# InPortIndication.net
KiCad netlist of a schematic drawn in Altium Designer
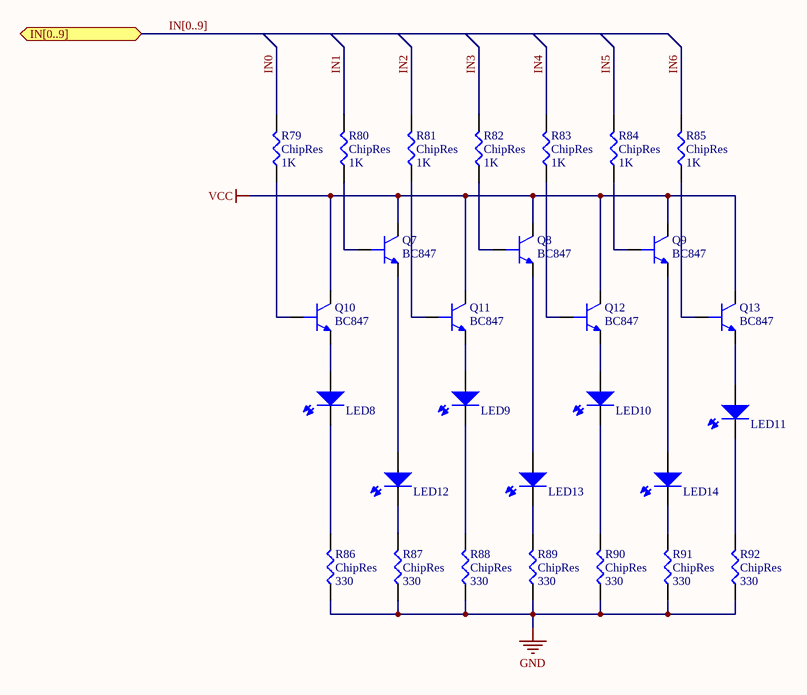
[diagram p0: InPortIndication.SchDoc]

(export (version "E")
  (design (tool "Eeschema 10.0.6"))
  (components
    (comp (ref "LED8") (value "LED 0603") (footprint "LED 0603") (libsource (lib "LEDs") (part "LED0603")))
    (comp (ref "LED9") (value "LED 0603") (footprint "LED 0603") (libsource (lib "LEDs") (part "LED0603")))
    (comp (ref "LED10") (value "LED 0603") (footprint "LED 0603") (libsource (lib "LEDs") (part "LED0603")))
    (comp (ref "LED11") (value "LED 0603") (footprint "LED 0603") (libsource (lib "LEDs") (part "LED0603")))
    (comp (ref "LED12") (value "LED 0603") (footprint "LED 0603") (libsource (lib "LEDs") (part "LED0603")))
    (comp (ref "LED13") (value "LED 0603") (footprint "LED 0603") (libsource (lib "LEDs") (part "LED0603")))
    (comp (ref "LED14") (value "LED 0603") (footprint "LED 0603") (libsource (lib "LEDs") (part "LED0603")))
    (comp (ref "Q7")
      (value "BC847")
      (footprint "SOT23")
      (description "NPN transistor")
      (libsource (lib "BJT") (part "BC847"))
    )
    (comp (ref "Q8")
      (value "BC847")
      (footprint "SOT23")
      (description "NPN transistor")
      (libsource (lib "BJT") (part "BC847"))
    )
    (comp (ref "Q9")
      (value "BC847")
      (footprint "SOT23")
      (description "NPN transistor")
      (libsource (lib "BJT") (part "BC847"))
    )
    (comp (ref "Q10")
      (value "BC847")
      (footprint "SOT23")
      (description "NPN transistor")
      (libsource (lib "BJT") (part "BC847"))
    )
    (comp (ref "Q11")
      (value "BC847")
      (footprint "SOT23")
      (description "NPN transistor")
      (libsource (lib "BJT") (part "BC847"))
    )
    (comp (ref "Q12")
      (value "BC847")
      (footprint "SOT23")
      (description "NPN transistor")
      (libsource (lib "BJT") (part "BC847"))
    )
    (comp (ref "Q13")
      (value "BC847")
      (footprint "SOT23")
      (description "NPN transistor")
      (libsource (lib "BJT") (part "BC847"))
    )
    (comp (ref "R79")
      (value "ChipRes")
      (footprint "RES0805")
      (description "Chip resistor")
      (fields (field (name "ALTIUM_VALUE") "1K"))
      (libsource (lib "Common Devices") (part "ChipRes"))
    )
    (comp (ref "R80")
      (value "ChipRes")
      (footprint "RES0805")
      (description "Chip resistor")
      (fields (field (name "ALTIUM_VALUE") "1K"))
      (libsource (lib "Common Devices") (part "ChipRes"))
    )
    (comp (ref "R81")
      (value "ChipRes")
      (footprint "RES0805")
      (description "Chip resistor")
      (fields (field (name "ALTIUM_VALUE") "1K"))
      (libsource (lib "Common Devices") (part "ChipRes"))
    )
    (comp (ref "R82")
      (value "ChipRes")
      (footprint "RES0805")
      (description "Chip resistor")
      (fields (field (name "ALTIUM_VALUE") "1K"))
      (libsource (lib "Common Devices") (part "ChipRes"))
    )
    (comp (ref "R83")
      (value "ChipRes")
      (footprint "RES0805")
      (description "Chip resistor")
      (fields (field (name "ALTIUM_VALUE") "1K"))
      (libsource (lib "Common Devices") (part "ChipRes"))
    )
    (comp (ref "R84")
      (value "ChipRes")
      (footprint "RES0805")
      (description "Chip resistor")
      (fields (field (name "ALTIUM_VALUE") "1K"))
      (libsource (lib "Common Devices") (part "ChipRes"))
    )
    (comp (ref "R85")
      (value "ChipRes")
      (footprint "RES0805")
      (description "Chip resistor")
      (fields (field (name "ALTIUM_VALUE") "1K"))
      (libsource (lib "Common Devices") (part "ChipRes"))
    )
    (comp (ref "R86")
      (value "ChipRes")
      (footprint "RES0805")
      (description "Chip resistor")
      (fields (field (name "ALTIUM_VALUE") "330"))
      (libsource (lib "Common Devices") (part "ChipRes"))
    )
    (comp (ref "R87")
      (value "ChipRes")
      (footprint "RES0805")
      (description "Chip resistor")
      (fields (field (name "ALTIUM_VALUE") "330"))
      (libsource (lib "Common Devices") (part "ChipRes"))
    )
    (comp (ref "R88")
      (value "ChipRes")
      (footprint "RES0805")
      (description "Chip resistor")
      (fields (field (name "ALTIUM_VALUE") "330"))
      (libsource (lib "Common Devices") (part "ChipRes"))
    )
    (comp (ref "R89")
      (value "ChipRes")
      (footprint "RES0805")
      (description "Chip resistor")
      (fields (field (name "ALTIUM_VALUE") "330"))
      (libsource (lib "Common Devices") (part "ChipRes"))
    )
    (comp (ref "R90")
      (value "ChipRes")
      (footprint "RES0805")
      (description "Chip resistor")
      (fields (field (name "ALTIUM_VALUE") "330"))
      (libsource (lib "Common Devices") (part "ChipRes"))
    )
    (comp (ref "R91")
      (value "ChipRes")
      (footprint "RES0805")
      (description "Chip resistor")
      (fields (field (name "ALTIUM_VALUE") "330"))
      (libsource (lib "Common Devices") (part "ChipRes"))
    )
    (comp (ref "R92")
      (value "ChipRes")
      (footprint "RES0805")
      (description "Chip resistor")
      (fields (field (name "ALTIUM_VALUE") "330"))
      (libsource (lib "Common Devices") (part "ChipRes"))
    )
  )
  (nets
    (net (code "4") (name "/IN0") (class "Default") (node (ref "R79") (pin "2") (pintype "passive")))
    (net (code "5") (name "/IN1") (class "Default") (node (ref "R80") (pin "2") (pintype "passive")))
    (net (code "6") (name "/IN2") (class "Default") (node (ref "R81") (pin "2") (pintype "passive")))
    (net (code "7") (name "/IN3") (class "Default") (node (ref "R82") (pin "2") (pintype "passive")))
    (net (code "8") (name "/IN4") (class "Default") (node (ref "R83") (pin "2") (pintype "passive")))
    (net (code "9") (name "/IN5") (class "Default") (node (ref "R84") (pin "2") (pintype "passive")))
    (net (code "10") (name "/IN6") (class "Default") (node (ref "R85") (pin "2") (pintype "passive")))
    (net (code "12") (name "GND") (class "Default")
      (node (ref "R86") (pin "1") (pintype "passive"))
      (node (ref "R87") (pin "1") (pintype "passive"))
      (node (ref "R88") (pin "1") (pintype "passive"))
      (node (ref "R89") (pin "1") (pintype "passive"))
      (node (ref "R90") (pin "1") (pintype "passive"))
      (node (ref "R91") (pin "1") (pintype "passive"))
      (node (ref "R92") (pin "1") (pintype "passive"))
    )
    (net (code "13") (name "Net-(LED8-Pad1)") (class "Default")
      (node (ref "LED8") (pin "1") (pinfunction "1_1") (pintype "passive"))
      (node (ref "R86") (pin "2") (pintype "passive"))
    )
    (net (code "14") (name "Net-(LED8-Pad2)") (class "Default")
      (node (ref "LED8") (pin "2") (pinfunction "2_2") (pintype "passive"))
      (node (ref "Q10") (pin "2") (pinfunction "2_2") (pintype "passive"))
    )
    (net (code "15") (name "Net-(LED9-Pad1)") (class "Default")
      (node (ref "LED9") (pin "1") (pinfunction "1_1") (pintype "passive"))
      (node (ref "R88") (pin "2") (pintype "passive"))
    )
    (net (code "16") (name "Net-(LED9-Pad2)") (class "Default")
      (node (ref "LED9") (pin "2") (pinfunction "2_2") (pintype "passive"))
      (node (ref "Q11") (pin "2") (pinfunction "2_2") (pintype "passive"))
    )
    (net (code "17") (name "Net-(LED10-Pad1)") (class "Default")
      (node (ref "LED10") (pin "1") (pinfunction "1_1") (pintype "passive"))
      (node (ref "R90") (pin "2") (pintype "passive"))
    )
    (net (code "18") (name "Net-(LED10-Pad2)") (class "Default")
      (node (ref "LED10") (pin "2") (pinfunction "2_2") (pintype "passive"))
      (node (ref "Q12") (pin "2") (pinfunction "2_2") (pintype "passive"))
    )
    (net (code "19") (name "Net-(LED11-Pad1)") (class "Default")
      (node (ref "LED11") (pin "1") (pinfunction "1_1") (pintype "passive"))
      (node (ref "R92") (pin "2") (pintype "passive"))
    )
    (net (code "20") (name "Net-(LED11-Pad2)") (class "Default")
      (node (ref "LED11") (pin "2") (pinfunction "2_2") (pintype "passive"))
      (node (ref "Q13") (pin "2") (pinfunction "2_2") (pintype "passive"))
    )
    (net (code "21") (name "Net-(LED12-Pad1)") (class "Default")
      (node (ref "LED12") (pin "1") (pinfunction "1_1") (pintype "passive"))
      (node (ref "R87") (pin "2") (pintype "passive"))
    )
    (net (code "22") (name "Net-(LED12-Pad2)") (class "Default")
      (node (ref "LED12") (pin "2") (pinfunction "2_2") (pintype "passive"))
      (node (ref "Q7") (pin "2") (pinfunction "2_2") (pintype "passive"))
    )
    (net (code "23") (name "Net-(LED13-Pad1)") (class "Default")
      (node (ref "LED13") (pin "1") (pinfunction "1_1") (pintype "passive"))
      (node (ref "R89") (pin "2") (pintype "passive"))
    )
    (net (code "24") (name "Net-(LED13-Pad2)") (class "Default")
      (node (ref "LED13") (pin "2") (pinfunction "2_2") (pintype "passive"))
      (node (ref "Q8") (pin "2") (pinfunction "2_2") (pintype "passive"))
    )
    (net (code "25") (name "Net-(LED14-Pad1)") (class "Default")
      (node (ref "LED14") (pin "1") (pinfunction "1_1") (pintype "passive"))
      (node (ref "R91") (pin "2") (pintype "passive"))
    )
    (net (code "26") (name "Net-(LED14-Pad2)") (class "Default")
      (node (ref "LED14") (pin "2") (pinfunction "2_2") (pintype "passive"))
      (node (ref "Q9") (pin "2") (pinfunction "2_2") (pintype "passive"))
    )
    (net (code "27") (name "Net-(Q7-Pad1)") (class "Default")
      (node (ref "Q7") (pin "1") (pinfunction "1_1") (pintype "passive"))
      (node (ref "R80") (pin "1") (pintype "passive"))
    )
    (net (code "28") (name "Net-(Q8-Pad1)") (class "Default")
      (node (ref "Q8") (pin "1") (pinfunction "1_1") (pintype "passive"))
      (node (ref "R82") (pin "1") (pintype "passive"))
    )
    (net (code "29") (name "Net-(Q9-Pad1)") (class "Default")
      (node (ref "Q9") (pin "1") (pinfunction "1_1") (pintype "passive"))
      (node (ref "R84") (pin "1") (pintype "passive"))
    )
    (net (code "30") (name "Net-(Q10-Pad1)") (class "Default")
      (node (ref "Q10") (pin "1") (pinfunction "1_1") (pintype "passive"))
      (node (ref "R79") (pin "1") (pintype "passive"))
    )
    (net (code "31") (name "Net-(Q11-Pad1)") (class "Default")
      (node (ref "Q11") (pin "1") (pinfunction "1_1") (pintype "passive"))
      (node (ref "R81") (pin "1") (pintype "passive"))
    )
    (net (code "32") (name "Net-(Q12-Pad1)") (class "Default")
      (node (ref "Q12") (pin "1") (pinfunction "1_1") (pintype "passive"))
      (node (ref "R83") (pin "1") (pintype "passive"))
    )
    (net (code "33") (name "Net-(Q13-Pad1)") (class "Default")
      (node (ref "Q13") (pin "1") (pinfunction "1_1") (pintype "passive"))
      (node (ref "R85") (pin "1") (pintype "passive"))
    )
    (net (code "34") (name "VCC") (class "Default")
      (node (ref "Q10") (pin "3") (pinfunction "3_3") (pintype "passive"))
      (node (ref "Q11") (pin "3") (pinfunction "3_3") (pintype "passive"))
      (node (ref "Q12") (pin "3") (pinfunction "3_3") (pintype "passive"))
      (node (ref "Q13") (pin "3") (pinfunction "3_3") (pintype "passive"))
      (node (ref "Q7") (pin "3") (pinfunction "3_3") (pintype "passive"))
      (node (ref "Q8") (pin "3") (pinfunction "3_3") (pintype "passive"))
      (node (ref "Q9") (pin "3") (pinfunction "3_3") (pintype "passive"))
    )
  )
)
